# 555_Monostable.net
KiCad netlist of a schematic drawn in EAGLE
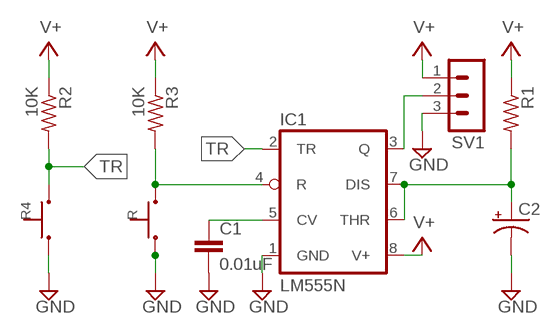
[diagram p0: schematic, sheet 1]

(export (version "E")
  (design (tool "Eeschema 10.0.6"))
  (components
    (comp (ref "C1")
      (value "0.01uF")
      (footprint "eagle-import:C025-025X050")
      (libsource (lib "eagle-import") (part "C-EU025-025X050"))
    )
    (comp (ref "C2")
      (value "CPOL-USE1.8-4")
      (footprint "eagle-import:E1,8-4")
      (libsource (lib "eagle-import") (part "CPOL-USE1.8-4"))
    )
    (comp (ref "IC1")
      (value "LM555N")
      (footprint "eagle-import:DIL08")
      (libsource (lib "eagle-import") (part "555NLM"))
    )
    (comp (ref "R")
      (value "2PIN")
      (footprint "eagle-import:2PIN")
      (libsource (lib "eagle-import") (part "2PIN"))
    )
    (comp (ref "R1")
      (value "R-US_0207/10")
      (footprint "eagle-import:0207_10")
      (libsource (lib "eagle-import") (part "R-US_0207/10"))
    )
    (comp (ref "R2")
      (value "10K")
      (footprint "eagle-import:0207_10")
      (libsource (lib "eagle-import") (part "R-US_0207/10"))
    )
    (comp (ref "R3")
      (value "10K")
      (footprint "eagle-import:0207_10")
      (libsource (lib "eagle-import") (part "R-US_0207/10"))
    )
    (comp (ref "R4")
      (value "2PIN")
      (footprint "eagle-import:2PIN")
      (libsource (lib "eagle-import") (part "2PIN"))
    )
    (comp (ref "SV1")
      (value "MA03-1")
      (footprint "eagle-import:MA03-1")
      (libsource (lib "eagle-import") (part "MA03-1"))
    )
  )
  (nets
    (net (code "1") (name "GND") (class "Default")
      (node (ref "C1") (pin "2") (pinfunction "2_2") (pintype "passive"))
      (node (ref "C2") (pin "-") (pinfunction "-_-") (pintype "passive"))
      (node (ref "IC1") (pin "1") (pinfunction "GND_1") (pintype "power_in"))
      (node (ref "R") (pin "1") (pinfunction "P$1_1") (pintype "bidirectional"))
      (node (ref "R4") (pin "1") (pinfunction "P$1_1") (pintype "bidirectional"))
      (node (ref "SV1") (pin "3") (pinfunction "3_3") (pintype "passive"))
    )
    (net (code "2") (name "Net-(IC1-CV)") (class "Default")
      (node (ref "C1") (pin "1") (pinfunction "1_1") (pintype "passive"))
      (node (ref "IC1") (pin "5") (pinfunction "CV_5") (pintype "input"))
    )
    (net (code "3") (name "Net-(IC1-DIS)") (class "Default")
      (node (ref "C2") (pin "+") (pinfunction "+_+") (pintype "passive"))
      (node (ref "IC1") (pin "6") (pinfunction "THR_6") (pintype "input"))
      (node (ref "IC1") (pin "7") (pinfunction "DIS_7") (pintype "input"))
      (node (ref "R1") (pin "2") (pinfunction "2_2") (pintype "passive"))
    )
    (net (code "4") (name "Net-(IC1-Q)") (class "Default")
      (node (ref "IC1") (pin "3") (pinfunction "Q_3") (pintype "output"))
      (node (ref "SV1") (pin "2") (pinfunction "2_2") (pintype "passive"))
    )
    (net (code "5") (name "Net-(IC1-R)") (class "Default")
      (node (ref "IC1") (pin "4") (pinfunction "R_4") (pintype "input"))
      (node (ref "R") (pin "2") (pinfunction "P$2_2") (pintype "bidirectional"))
      (node (ref "R3") (pin "2") (pinfunction "2_2") (pintype "passive"))
    )
    (net (code "6") (name "TR") (class "Default")
      (node (ref "IC1") (pin "2") (pinfunction "TR_2") (pintype "input"))
      (node (ref "R2") (pin "2") (pinfunction "2_2") (pintype "passive"))
      (node (ref "R4") (pin "2") (pinfunction "P$2_2") (pintype "bidirectional"))
    )
    (net (code "7") (name "V+") (class "Default")
      (node (ref "IC1") (pin "8") (pinfunction "V+_8") (pintype "power_in"))
      (node (ref "R1") (pin "1") (pinfunction "1_1") (pintype "passive"))
      (node (ref "R2") (pin "1") (pinfunction "1_1") (pintype "passive"))
      (node (ref "R3") (pin "1") (pinfunction "1_1") (pintype "passive"))
      (node (ref "SV1") (pin "1") (pinfunction "1_1") (pintype "passive"))
    )
  )
)
